# MCU.net
KiCad netlist of a schematic drawn in Altium Designer
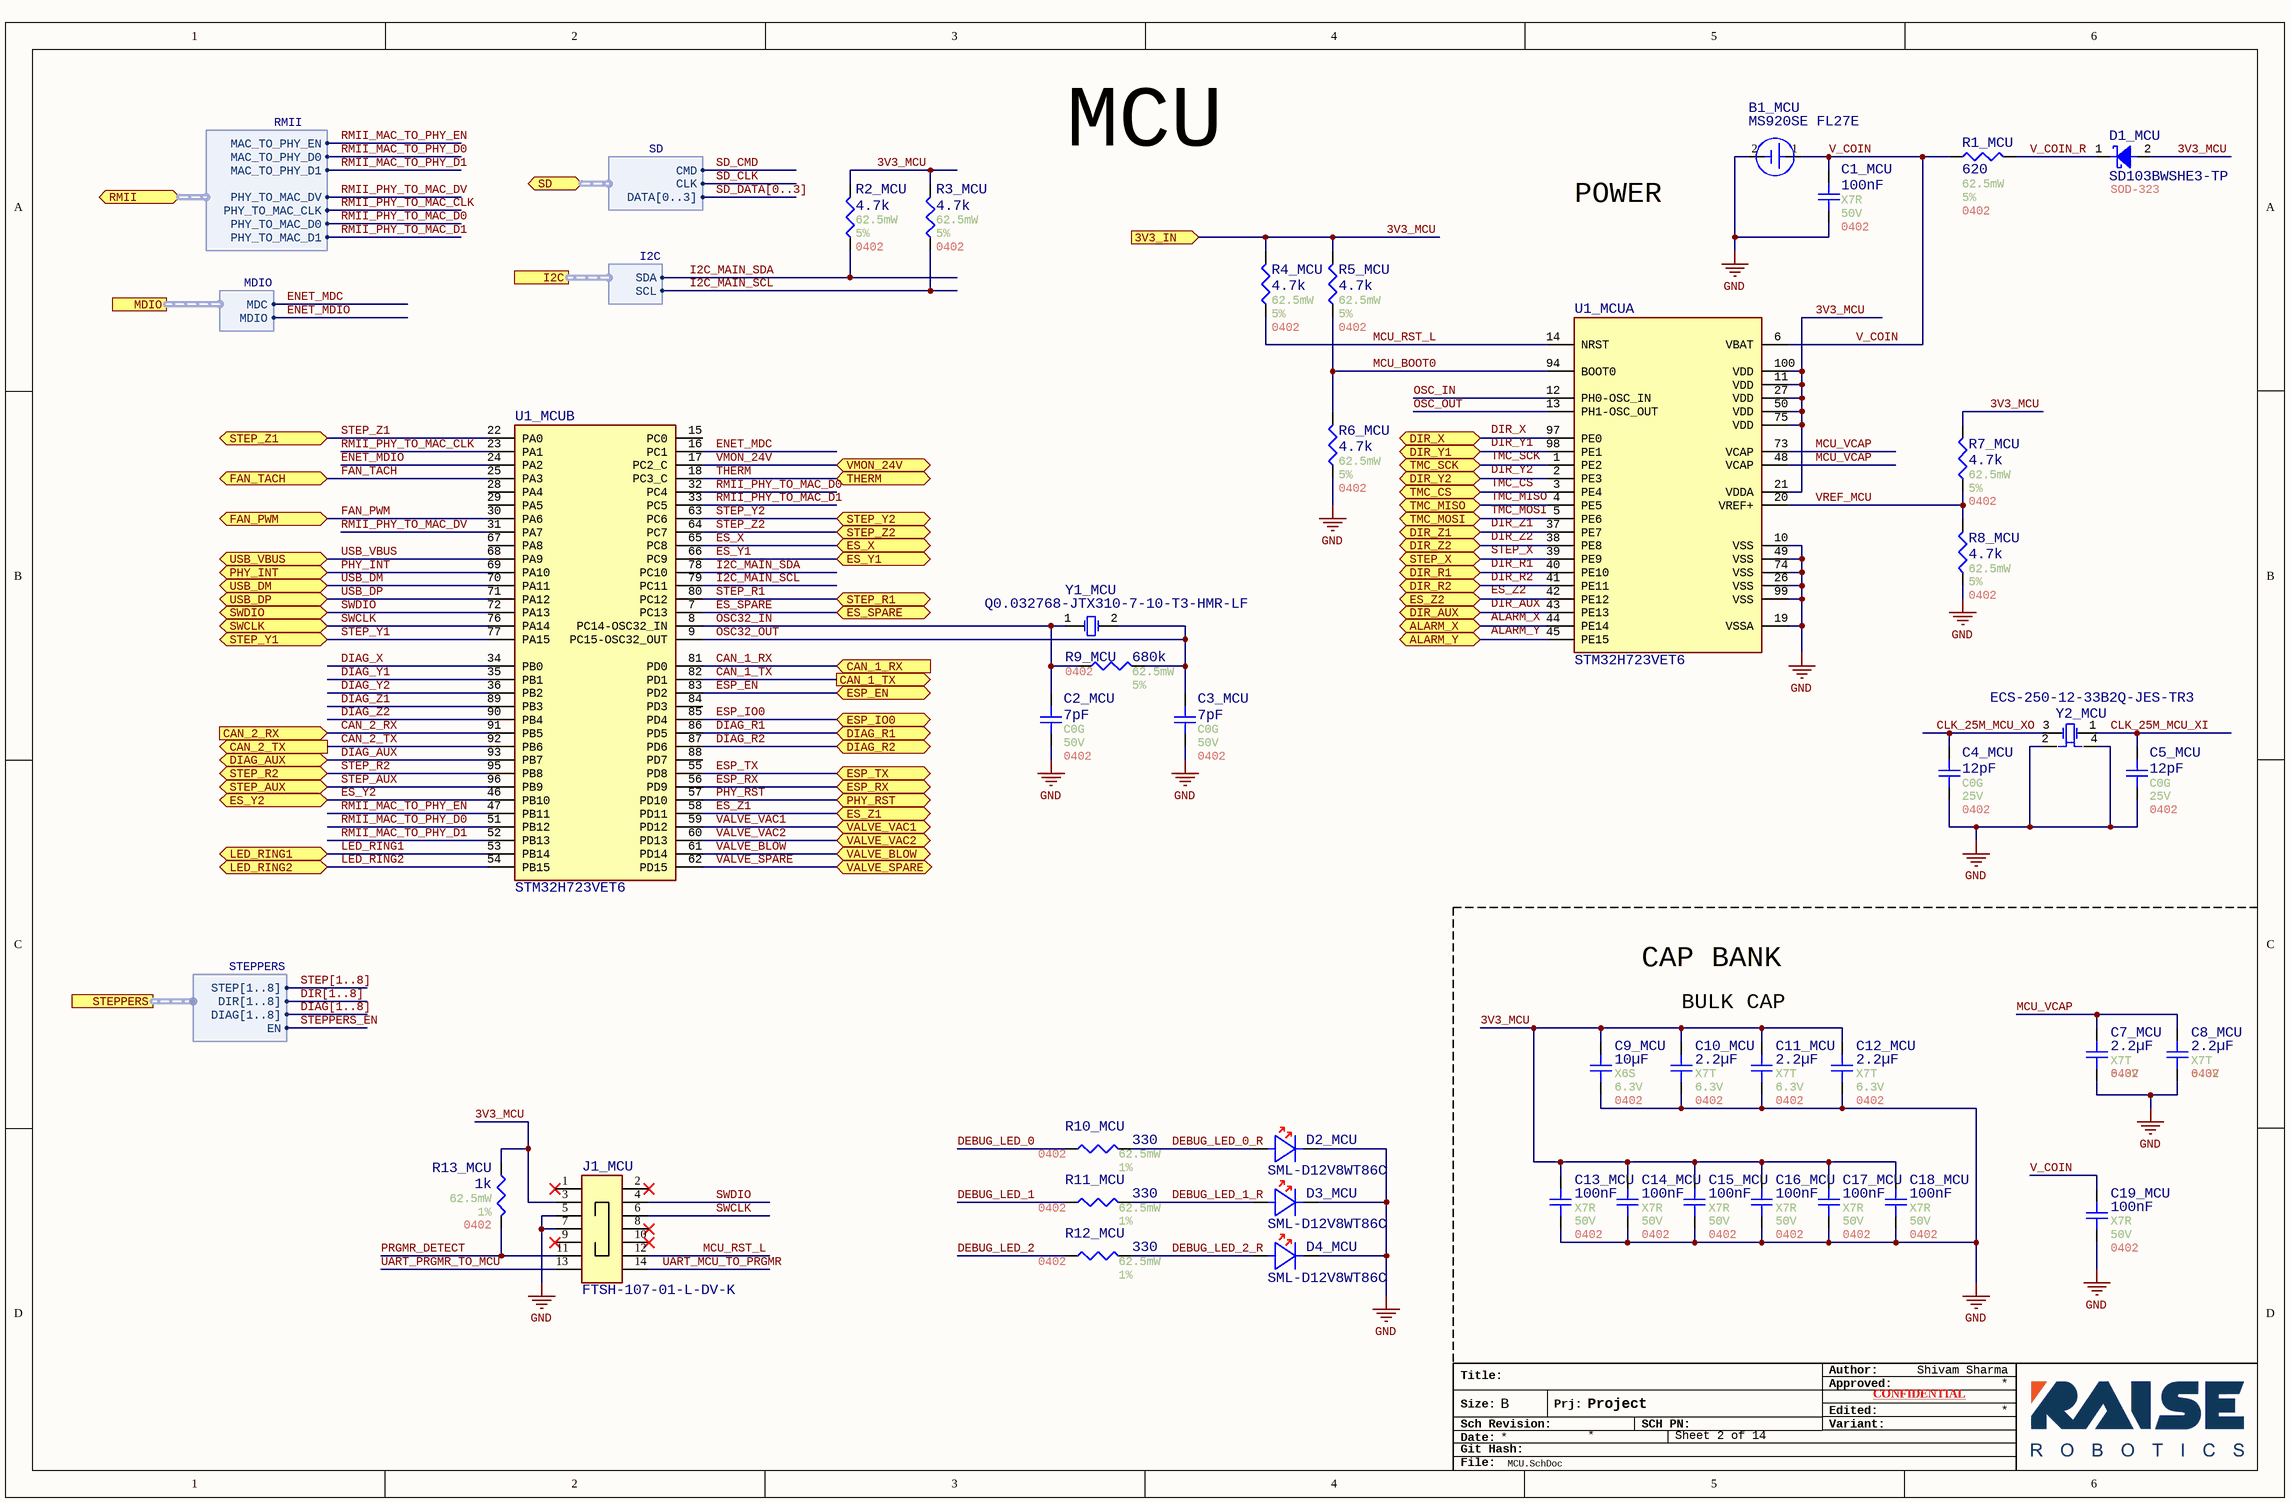
[diagram p0: MCU.SchDoc]

(export (version "E")
  (design (tool "Eeschema 10.0.6"))
  (components
    (comp (ref "B1_MCU")
      (value "MS920SE FL27E")
      (footprint "MS920SE-FL27E")
      (description "Secondary Battery, Manganese Silicon Lithium, 3V, 0.011Ah")
      (libsource (lib "Raise Robotics") (part "Coin Cell"))
    )
    (comp (ref "C1_MCU")
      (value "100nF")
      (footprint "Generic 0402 capacitor")
      (fields
        (field (name "TEMPERATURE COEFFICIENT") "X7R")
        (field (name "VOLTAGE RATING") "50V")
        (field (name "CASE/PACKAGE") "0402")
        (field (name "TOLERANCE") "10%")
        (field (name "Comment") "GRT155R71H104KE01D")
      )
      (libsource (lib "Raise Robotics") (part "Unpolarized Capacitor"))
    )
    (comp (ref "C2_MCU")
      (value "7pF")
      (footprint "Generic 0402 capacitor")
      (fields
        (field (name "TEMPERATURE COEFFICIENT") "C0G")
        (field (name "VOLTAGE RATING") "50V")
        (field (name "CASE/PACKAGE") "0402")
        (field (name "TOLERANCE") "3.5%")
        (field (name "Comment") "GCM1555C1H7R0CA16J")
      )
      (libsource (lib "Raise Robotics") (part "Unpolarized Capacitor"))
    )
    (comp (ref "C3_MCU")
      (value "7pF")
      (footprint "Generic 0402 capacitor")
      (fields
        (field (name "TEMPERATURE COEFFICIENT") "C0G")
        (field (name "VOLTAGE RATING") "50V")
        (field (name "CASE/PACKAGE") "0402")
        (field (name "TOLERANCE") "3.5%")
        (field (name "Comment") "GCM1555C1H7R0CA16J")
      )
      (libsource (lib "Raise Robotics") (part "Unpolarized Capacitor"))
    )
    (comp (ref "C4_MCU")
      (value "12pF")
      (footprint "Generic 0402 capacitor")
      (fields
        (field (name "TEMPERATURE COEFFICIENT") "C0G")
        (field (name "VOLTAGE RATING") "25V")
        (field (name "CASE/PACKAGE") "0402")
        (field (name "TOLERANCE") "5%")
        (field (name "Comment") "GRT1555C1E120JA02J")
      )
      (libsource (lib "Raise Robotics") (part "Unpolarized Capacitor"))
    )
    (comp (ref "C5_MCU")
      (value "12pF")
      (footprint "Generic 0402 capacitor")
      (fields
        (field (name "TEMPERATURE COEFFICIENT") "C0G")
        (field (name "VOLTAGE RATING") "25V")
        (field (name "CASE/PACKAGE") "0402")
        (field (name "TOLERANCE") "5%")
        (field (name "Comment") "GRT1555C1E120JA02J")
      )
      (libsource (lib "Raise Robotics") (part "Unpolarized Capacitor"))
    )
    (comp (ref "C7_MCU")
      (value "2.2µF")
      (footprint "Generic 0402 capacitor")
      (description "Mlcc, 2.2 Uf, # 20 %, 0402, 6.3V, X7T, T&r Q200")
      (fields
        (field (name "TEMPERATURE COEFFICIENT") "X7T")
        (field (name "VOLTAGE RATING") "6.3V")
        (field (name "CASE/PACKAGE") "0402")
        (field (name "TOLERANCE") "20%")
        (field (name "Comment") "MAASJ105CD7225MFCA01")
      )
      (libsource (lib "Raise Robotics") (part "Unpolarized Capacitor"))
    )
    (comp (ref "C8_MCU")
      (value "2.2µF")
      (footprint "Generic 0402 capacitor")
      (description "Mlcc, 2.2 Uf, # 20 %, 0402, 6.3V, X7T, T&r Q200")
      (fields
        (field (name "TEMPERATURE COEFFICIENT") "X7T")
        (field (name "VOLTAGE RATING") "6.3V")
        (field (name "CASE/PACKAGE") "0402")
        (field (name "TOLERANCE") "20%")
        (field (name "Comment") "MAASJ105CD7225MFCA01")
      )
      (libsource (lib "Raise Robotics") (part "Unpolarized Capacitor"))
    )
    (comp (ref "C9_MCU")
      (value "10µF")
      (footprint "Generic 0402 capacitor")
      (description "Multilayer Ceramic Capacitors MLCC - SMD/SMT 0402 10uF 6.3VDC 20% X6S AEC-Q200")
      (fields
        (field (name "TEMPERATURE COEFFICIENT") "X6S")
        (field (name "VOLTAGE RATING") "6.3V")
        (field (name "CASE/PACKAGE") "0402")
        (field (name "TOLERANCE") "20%")
        (field (name "Comment") "GRT155C80J106ME13J")
      )
      (libsource (lib "Raise Robotics") (part "Unpolarized Capacitor"))
    )
    (comp (ref "C10_MCU")
      (value "2.2µF")
      (footprint "Generic 0402 capacitor")
      (description "Mlcc, 2.2 Uf, # 20 %, 0402, 6.3V, X7T, T&r Q200")
      (fields
        (field (name "TEMPERATURE COEFFICIENT") "X7T")
        (field (name "VOLTAGE RATING") "6.3V")
        (field (name "CASE/PACKAGE") "0402")
        (field (name "TOLERANCE") "20%")
        (field (name "Comment") "MAASJ105CD7225MFCA01")
      )
      (libsource (lib "Raise Robotics") (part "Unpolarized Capacitor"))
    )
    (comp (ref "C11_MCU")
      (value "2.2µF")
      (footprint "Generic 0402 capacitor")
      (description "Mlcc, 2.2 Uf, # 20 %, 0402, 6.3V, X7T, T&r Q200")
      (fields
        (field (name "TEMPERATURE COEFFICIENT") "X7T")
        (field (name "VOLTAGE RATING") "6.3V")
        (field (name "CASE/PACKAGE") "0402")
        (field (name "TOLERANCE") "20%")
        (field (name "Comment") "MAASJ105CD7225MFCA01")
      )
      (libsource (lib "Raise Robotics") (part "Unpolarized Capacitor"))
    )
    (comp (ref "C12_MCU")
      (value "2.2µF")
      (footprint "Generic 0402 capacitor")
      (description "Mlcc, 2.2 Uf, # 20 %, 0402, 6.3V, X7T, T&r Q200")
      (fields
        (field (name "TEMPERATURE COEFFICIENT") "X7T")
        (field (name "VOLTAGE RATING") "6.3V")
        (field (name "CASE/PACKAGE") "0402")
        (field (name "TOLERANCE") "20%")
        (field (name "Comment") "MAASJ105CD7225MFCA01")
      )
      (libsource (lib "Raise Robotics") (part "Unpolarized Capacitor"))
    )
    (comp (ref "C13_MCU")
      (value "100nF")
      (footprint "Generic 0402 capacitor")
      (fields
        (field (name "TEMPERATURE COEFFICIENT") "X7R")
        (field (name "VOLTAGE RATING") "50V")
        (field (name "CASE/PACKAGE") "0402")
        (field (name "TOLERANCE") "10%")
        (field (name "Comment") "GRT155R71H104KE01D")
      )
      (libsource (lib "Raise Robotics") (part "Unpolarized Capacitor"))
    )
    (comp (ref "C14_MCU")
      (value "100nF")
      (footprint "Generic 0402 capacitor")
      (fields
        (field (name "TEMPERATURE COEFFICIENT") "X7R")
        (field (name "VOLTAGE RATING") "50V")
        (field (name "CASE/PACKAGE") "0402")
        (field (name "TOLERANCE") "10%")
        (field (name "Comment") "GRT155R71H104KE01D")
      )
      (libsource (lib "Raise Robotics") (part "Unpolarized Capacitor"))
    )
    (comp (ref "C15_MCU")
      (value "100nF")
      (footprint "Generic 0402 capacitor")
      (fields
        (field (name "TEMPERATURE COEFFICIENT") "X7R")
        (field (name "VOLTAGE RATING") "50V")
        (field (name "CASE/PACKAGE") "0402")
        (field (name "TOLERANCE") "10%")
        (field (name "Comment") "GRT155R71H104KE01D")
      )
      (libsource (lib "Raise Robotics") (part "Unpolarized Capacitor"))
    )
    (comp (ref "C16_MCU")
      (value "100nF")
      (footprint "Generic 0402 capacitor")
      (fields
        (field (name "TEMPERATURE COEFFICIENT") "X7R")
        (field (name "VOLTAGE RATING") "50V")
        (field (name "CASE/PACKAGE") "0402")
        (field (name "TOLERANCE") "10%")
        (field (name "Comment") "GRT155R71H104KE01D")
      )
      (libsource (lib "Raise Robotics") (part "Unpolarized Capacitor"))
    )
    (comp (ref "C17_MCU")
      (value "100nF")
      (footprint "Generic 0402 capacitor")
      (fields
        (field (name "TEMPERATURE COEFFICIENT") "X7R")
        (field (name "VOLTAGE RATING") "50V")
        (field (name "CASE/PACKAGE") "0402")
        (field (name "TOLERANCE") "10%")
        (field (name "Comment") "GRT155R71H104KE01D")
      )
      (libsource (lib "Raise Robotics") (part "Unpolarized Capacitor"))
    )
    (comp (ref "C18_MCU")
      (value "100nF")
      (footprint "Generic 0402 capacitor")
      (fields
        (field (name "TEMPERATURE COEFFICIENT") "X7R")
        (field (name "VOLTAGE RATING") "50V")
        (field (name "CASE/PACKAGE") "0402")
        (field (name "TOLERANCE") "10%")
        (field (name "Comment") "GRT155R71H104KE01D")
      )
      (libsource (lib "Raise Robotics") (part "Unpolarized Capacitor"))
    )
    (comp (ref "C19_MCU")
      (value "100nF")
      (footprint "Generic 0402 capacitor")
      (fields
        (field (name "TEMPERATURE COEFFICIENT") "X7R")
        (field (name "VOLTAGE RATING") "50V")
        (field (name "CASE/PACKAGE") "0402")
        (field (name "TOLERANCE") "10%")
        (field (name "Comment") "GRT155R71H104KE01D")
      )
      (libsource (lib "Raise Robotics") (part "Unpolarized Capacitor"))
    )
    (comp (ref "D1_MCU")
      (value "SD103BWSHE3-TP")
      (footprint "SOD-323")
      (description "Rectifier Diode, Schottky, 1 Phase, 1 Element, 0.35A, 30V V(RRM), Silicon")
      (fields (field (name "CASE/PACKAGE") "SOD-323"))
      (libsource (lib "Raise Robotics") (part "Generic 2 pin Diode"))
    )
    (comp (ref "D2_MCU")
      (value "SML-D12V8WT86C")
      (footprint "FP-SML-D12-MFG")
      (description "Red 630nm LED Indication - Discrete 2.2V 0603 (1608 Metric)")
      (libsource (lib "Raise Robotics") (part "LED Red"))
    )
    (comp (ref "D3_MCU")
      (value "SML-D12V8WT86C")
      (footprint "FP-SML-D12-MFG")
      (description "Red 630nm LED Indication - Discrete 2.2V 0603 (1608 Metric)")
      (libsource (lib "Raise Robotics") (part "LED Red"))
    )
    (comp (ref "D4_MCU")
      (value "SML-D12V8WT86C")
      (footprint "FP-SML-D12-MFG")
      (description "Red 630nm LED Indication - Discrete 2.2V 0603 (1608 Metric)")
      (libsource (lib "Raise Robotics") (part "LED Red"))
    )
    (comp (ref "J1_MCU")
      (value "FTSH-107-01-L-DV-K")
      (footprint "FTSH-107-01-L-DV-K-TR")
      (fields (field (name "MANUFACTURER") "Samtec"))
      (libsource (lib "Raise Robotics") (part "FTSH-107-01-L-DV-K-A"))
    )
    (comp (ref "R1_MCU")
      (value "620")
      (footprint "Generic 0402 Resistor")
      (fields
        (field (name "POWER") "62.5mW")
        (field (name "TOLERANCE") "5%")
        (field (name "CASE/PACKAGE") "0402")
        (field (name "Comment") "RC0402JR-07620RL")
      )
      (libsource (lib "Raise Robotics") (part "Resistor"))
    )
    (comp (ref "R2_MCU")
      (value "4.7k")
      (footprint "Generic 0402 Resistor")
      (fields
        (field (name "POWER") "62.5mW")
        (field (name "TOLERANCE") "5%")
        (field (name "CASE/PACKAGE") "0402")
        (field (name "MANUFACTURER PART NUMBER") "Blank")
        (field (name "Comment") "WR04X472JTL")
      )
      (libsource (lib "Raise Robotics") (part "Resistor"))
    )
    (comp (ref "R3_MCU")
      (value "4.7k")
      (footprint "Generic 0402 Resistor")
      (fields
        (field (name "POWER") "62.5mW")
        (field (name "TOLERANCE") "5%")
        (field (name "CASE/PACKAGE") "0402")
        (field (name "MANUFACTURER PART NUMBER") "Blank")
        (field (name "Comment") "WR04X472JTL")
      )
      (libsource (lib "Raise Robotics") (part "Resistor"))
    )
    (comp (ref "R4_MCU")
      (value "4.7k")
      (footprint "Generic 0402 Resistor")
      (fields
        (field (name "POWER") "62.5mW")
        (field (name "TOLERANCE") "5%")
        (field (name "CASE/PACKAGE") "0402")
        (field (name "MANUFACTURER PART NUMBER") "Blank")
        (field (name "Comment") "WR04X472JTL")
      )
      (libsource (lib "Raise Robotics") (part "Resistor"))
    )
    (comp (ref "R5_MCU")
      (value "4.7k")
      (footprint "Generic 0402 Resistor")
      (fields
        (field (name "POWER") "62.5mW")
        (field (name "TOLERANCE") "5%")
        (field (name "CASE/PACKAGE") "0402")
        (field (name "MANUFACTURER PART NUMBER") "Blank")
        (field (name "Comment") "WR04X472JTL")
      )
      (libsource (lib "Raise Robotics") (part "Resistor"))
    )
    (comp (ref "R6_MCU")
      (value "4.7k")
      (footprint "Generic 0402 Resistor")
      (fields
        (field (name "POWER") "62.5mW")
        (field (name "TOLERANCE") "5%")
        (field (name "CASE/PACKAGE") "0402")
        (field (name "MANUFACTURER PART NUMBER") "Blank")
        (field (name "Comment") "WR04X472JTL")
      )
      (libsource (lib "Raise Robotics") (part "Resistor"))
    )
    (comp (ref "R7_MCU")
      (value "4.7k")
      (footprint "Generic 0402 Resistor")
      (fields
        (field (name "POWER") "62.5mW")
        (field (name "TOLERANCE") "5%")
        (field (name "CASE/PACKAGE") "0402")
        (field (name "MANUFACTURER PART NUMBER") "Blank")
        (field (name "Comment") "WR04X472JTL")
      )
      (libsource (lib "Raise Robotics") (part "Resistor"))
    )
    (comp (ref "R8_MCU")
      (value "4.7k")
      (footprint "Generic 0402 Resistor")
      (fields
        (field (name "POWER") "62.5mW")
        (field (name "TOLERANCE") "5%")
        (field (name "CASE/PACKAGE") "0402")
        (field (name "MANUFACTURER PART NUMBER") "Blank")
        (field (name "Comment") "WR04X472JTL")
      )
      (libsource (lib "Raise Robotics") (part "Resistor"))
    )
    (comp (ref "R9_MCU")
      (value "680k")
      (footprint "Generic 0402 Resistor")
      (fields
        (field (name "POWER") "62.5mW")
        (field (name "TOLERANCE") "5%")
        (field (name "CASE/PACKAGE") "0402")
        (field (name "Comment") "AC0402JR-07680KL")
      )
      (libsource (lib "Raise Robotics") (part "Resistor"))
    )
    (comp (ref "R10_MCU")
      (value "330")
      (footprint "Generic 0402 Resistor")
      (description "Res Thick Film 0402 330 Ohm 1% 0.063W ±100ppm/°C Molded SMD Paper T/R")
      (fields
        (field (name "POWER") "62.5mW")
        (field (name "TOLERANCE") "1%")
        (field (name "CASE/PACKAGE") "0402")
        (field (name "Comment") "RMCF0402FT330R")
      )
      (libsource (lib "Raise Robotics") (part "Resistor"))
    )
    (comp (ref "R11_MCU")
      (value "330")
      (footprint "Generic 0402 Resistor")
      (description "Res Thick Film 0402 330 Ohm 1% 0.063W ±100ppm/°C Molded SMD Paper T/R")
      (fields
        (field (name "POWER") "62.5mW")
        (field (name "TOLERANCE") "1%")
        (field (name "CASE/PACKAGE") "0402")
        (field (name "Comment") "RMCF0402FT330R")
      )
      (libsource (lib "Raise Robotics") (part "Resistor"))
    )
    (comp (ref "R12_MCU")
      (value "330")
      (footprint "Generic 0402 Resistor")
      (description "Res Thick Film 0402 330 Ohm 1% 0.063W ±100ppm/°C Molded SMD Paper T/R")
      (fields
        (field (name "POWER") "62.5mW")
        (field (name "TOLERANCE") "1%")
        (field (name "CASE/PACKAGE") "0402")
        (field (name "Comment") "RMCF0402FT330R")
      )
      (libsource (lib "Raise Robotics") (part "Resistor"))
    )
    (comp (ref "R13_MCU")
      (value "1k")
      (footprint "Generic 0402 Resistor")
      (fields
        (field (name "POWER") "62.5mW")
        (field (name "TOLERANCE") "1%")
        (field (name "CASE/PACKAGE") "0402")
        (field (name "MANUFACTURER PART NUMBER") "Blank")
        (field (name "Comment") "WR04X1001FTL")
      )
      (libsource (lib "Raise Robotics") (part "Resistor"))
    )
    (comp (ref "U1_MCU")
      (value "STM32H723VET6")
      (footprint "STM32H723VxT")
      (description "MCU 32-bit ARM Cortex M7 RISC 512KB Flash 1.8V/2.5V/3.3V 100-Pin LQFP Tray")
      (libsource (lib "Raise Robotics") (part "STM32H723VET6"))
    )
    (comp (ref "Y1_MCU")
      (value "Q0.032768-JTX310-7-10-T3-HMR-LF")
      (footprint "JTX310")
      (description "Parallel - Fundamental Quartz Crystal, 0.032768MHz Nom")
      (libsource (lib "Raise Robotics") (part "XTAL-2"))
    )
    (comp (ref "Y2_MCU")
      (value "ECS-250-12-33B2Q-JES-TR3")
      (footprint "ECS-250-12-33B2Q-JES-TR3")
      (description "Crystal 25.000 Mhz 12PF SMD")
      (libsource (lib "") (part "XTAL-2_1"))
    )
  )
  (nets
    (net (code "30") (name "/3V3_MCU") (class "Default")
      (node (ref "C10_MCU") (pin "2") (pinfunction "2_2") (pintype "passive"))
      (node (ref "C11_MCU") (pin "2") (pinfunction "2_2") (pintype "passive"))
      (node (ref "C12_MCU") (pin "2") (pinfunction "2_2") (pintype "passive"))
      (node (ref "C13_MCU") (pin "2") (pinfunction "2_2") (pintype "passive"))
      (node (ref "C14_MCU") (pin "2") (pinfunction "2_2") (pintype "passive"))
      (node (ref "C15_MCU") (pin "2") (pinfunction "2_2") (pintype "passive"))
      (node (ref "C16_MCU") (pin "2") (pinfunction "2_2") (pintype "passive"))
      (node (ref "C17_MCU") (pin "2") (pinfunction "2_2") (pintype "passive"))
      (node (ref "C18_MCU") (pin "2") (pinfunction "2_2") (pintype "passive"))
      (node (ref "C9_MCU") (pin "2") (pinfunction "2_2") (pintype "passive"))
      (node (ref "D1_MCU") (pin "2") (pinfunction "A_2") (pintype "passive"))
      (node (ref "J1_MCU") (pin "3") (pinfunction "3_3") (pintype "passive"))
      (node (ref "R13_MCU") (pin "2") (pinfunction "2_2") (pintype "passive"))
      (node (ref "R2_MCU") (pin "2") (pinfunction "2_2") (pintype "passive"))
      (node (ref "R3_MCU") (pin "2") (pinfunction "2_2") (pintype "passive"))
      (node (ref "R4_MCU") (pin "2") (pinfunction "2_2") (pintype "passive"))
      (node (ref "R5_MCU") (pin "2") (pinfunction "2_2") (pintype "passive"))
      (node (ref "R7_MCU") (pin "2") (pinfunction "2_2") (pintype "passive"))
      (node (ref "U1_MCU") (pin "100") (pinfunction "VDD_100") (pintype "passive"))
      (node (ref "U1_MCU") (pin "11") (pinfunction "VDD_11") (pintype "passive"))
      (node (ref "U1_MCU") (pin "21") (pinfunction "VDDA_21") (pintype "passive"))
      (node (ref "U1_MCU") (pin "27") (pinfunction "VDD_27") (pintype "passive"))
      (node (ref "U1_MCU") (pin "50") (pinfunction "VDD_50") (pintype "passive"))
      (node (ref "U1_MCU") (pin "75") (pinfunction "VDD_75") (pintype "passive"))
    )
    (net (code "31") (name "/ALARM_X") (class "Default")
      (node (ref "U1_MCU") (pin "44") (pinfunction "PE14_44") (pintype "passive"))
    )
    (net (code "32") (name "/ALARM_Y") (class "Default")
      (node (ref "U1_MCU") (pin "45") (pinfunction "PE15_45") (pintype "passive"))
    )
    (net (code "33") (name "/CAN_1_RX") (class "Default")
      (node (ref "U1_MCU") (pin "81") (pinfunction "PD0_81") (pintype "passive"))
    )
    (net (code "34") (name "/CAN_1_TX") (class "Default")
      (node (ref "U1_MCU") (pin "82") (pinfunction "PD1_82") (pintype "passive"))
    )
    (net (code "35") (name "/CAN_2_RX") (class "Default")
      (node (ref "U1_MCU") (pin "91") (pinfunction "PB5_91") (pintype "passive"))
    )
    (net (code "36") (name "/CAN_2_TX") (class "Default")
      (node (ref "U1_MCU") (pin "92") (pinfunction "PB6_92") (pintype "passive"))
    )
    (net (code "37") (name "/CLK_25M_MCU_XI") (class "Default")
      (node (ref "C5_MCU") (pin "2") (pinfunction "2_2") (pintype "passive"))
      (node (ref "Y2_MCU") (pin "1") (pinfunction "1_1") (pintype "passive"))
    )
    (net (code "38") (name "/CLK_25M_MCU_XO") (class "Default")
      (node (ref "C4_MCU") (pin "2") (pinfunction "2_2") (pintype "passive"))
      (node (ref "Y2_MCU") (pin "3") (pinfunction "3_3") (pintype "passive"))
    )
    (net (code "39") (name "/DEBUG_LED_0") (class "Default")
      (node (ref "R10_MCU") (pin "1") (pinfunction "1_1") (pintype "passive"))
    )
    (net (code "40") (name "/DEBUG_LED_0_R") (class "Default")
      (node (ref "D2_MCU") (pin "2") (pinfunction "A_2") (pintype "passive"))
      (node (ref "R10_MCU") (pin "2") (pinfunction "2_2") (pintype "passive"))
    )
    (net (code "41") (name "/DEBUG_LED_1") (class "Default")
      (node (ref "R11_MCU") (pin "1") (pinfunction "1_1") (pintype "passive"))
    )
    (net (code "42") (name "/DEBUG_LED_1_R") (class "Default")
      (node (ref "D3_MCU") (pin "2") (pinfunction "A_2") (pintype "passive"))
      (node (ref "R11_MCU") (pin "2") (pinfunction "2_2") (pintype "passive"))
    )
    (net (code "43") (name "/DEBUG_LED_2") (class "Default")
      (node (ref "R12_MCU") (pin "1") (pinfunction "1_1") (pintype "passive"))
    )
    (net (code "44") (name "/DEBUG_LED_2_R") (class "Default")
      (node (ref "D4_MCU") (pin "2") (pinfunction "A_2") (pintype "passive"))
      (node (ref "R12_MCU") (pin "2") (pinfunction "2_2") (pintype "passive"))
    )
    (net (code "46") (name "/DIAG_AUX") (class "Default")
      (node (ref "U1_MCU") (pin "93") (pinfunction "PB7_93") (pintype "passive"))
    )
    (net (code "47") (name "/DIAG_R1") (class "Default")
      (node (ref "U1_MCU") (pin "86") (pinfunction "PD5_86") (pintype "passive"))
    )
    (net (code "48") (name "/DIAG_R2") (class "Default")
      (node (ref "U1_MCU") (pin "87") (pinfunction "PD6_87") (pintype "passive"))
    )
    (net (code "49") (name "/DIAG_X") (class "Default")
      (node (ref "U1_MCU") (pin "34") (pinfunction "PB0_34") (pintype "passive"))
    )
    (net (code "50") (name "/DIAG_Y1") (class "Default")
      (node (ref "U1_MCU") (pin "35") (pinfunction "PB1_35") (pintype "passive"))
    )
    (net (code "51") (name "/DIAG_Y2") (class "Default")
      (node (ref "U1_MCU") (pin "36") (pinfunction "PB2_36") (pintype "passive"))
    )
    (net (code "52") (name "/DIAG_Z1") (class "Default")
      (node (ref "U1_MCU") (pin "89") (pinfunction "PB3_89") (pintype "passive"))
    )
    (net (code "53") (name "/DIAG_Z2") (class "Default")
      (node (ref "U1_MCU") (pin "90") (pinfunction "PB4_90") (pintype "passive"))
    )
    (net (code "55") (name "/DIR_AUX") (class "Default")
      (node (ref "U1_MCU") (pin "43") (pinfunction "PE13_43") (pintype "passive"))
    )
    (net (code "56") (name "/DIR_R1") (class "Default")
      (node (ref "U1_MCU") (pin "40") (pinfunction "PE10_40") (pintype "passive"))
    )
    (net (code "57") (name "/DIR_R2") (class "Default")
      (node (ref "U1_MCU") (pin "41") (pinfunction "PE11_41") (pintype "passive"))
    )
    (net (code "58") (name "/DIR_X") (class "Default")
      (node (ref "U1_MCU") (pin "97") (pinfunction "PE0_97") (pintype "passive"))
    )
    (net (code "59") (name "/DIR_Y1") (class "Default")
      (node (ref "U1_MCU") (pin "98") (pinfunction "PE1_98") (pintype "passive"))
    )
    (net (code "60") (name "/DIR_Y2") (class "Default")
      (node (ref "U1_MCU") (pin "2") (pinfunction "PE3_2") (pintype "passive"))
    )
    (net (code "61") (name "/DIR_Z1") (class "Default")
      (node (ref "U1_MCU") (pin "37") (pinfunction "PE7_37") (pintype "passive"))
    )
    (net (code "62") (name "/DIR_Z2") (class "Default")
      (node (ref "U1_MCU") (pin "38") (pinfunction "PE8_38") (pintype "passive"))
    )
    (net (code "63") (name "/ENET_MDC") (class "Default")
      (node (ref "U1_MCU") (pin "16") (pinfunction "PC1_16") (pintype "passive"))
    )
    (net (code "64") (name "/ENET_MDIO") (class "Default")
      (node (ref "U1_MCU") (pin "24") (pinfunction "PA2_24") (pintype "passive"))
    )
    (net (code "65") (name "/ESP_EN") (class "Default")
      (node (ref "U1_MCU") (pin "83") (pinfunction "PD2_83") (pintype "passive"))
    )
    (net (code "66") (name "/ESP_IO0") (class "Default")
      (node (ref "U1_MCU") (pin "85") (pinfunction "PD4_85") (pintype "passive"))
    )
    (net (code "67") (name "/ESP_RX") (class "Default")
      (node (ref "U1_MCU") (pin "56") (pinfunction "PD9_56") (pintype "passive"))
    )
    (net (code "68") (name "/ESP_TX") (class "Default")
      (node (ref "U1_MCU") (pin "55") (pinfunction "PD8_55") (pintype "passive"))
    )
    (net (code "69") (name "/ES_SPARE") (class "Default")
      (node (ref "U1_MCU") (pin "7") (pinfunction "PC13_7") (pintype "passive"))
    )
    (net (code "70") (name "/ES_X") (class "Default")
      (node (ref "U1_MCU") (pin "65") (pinfunction "PC8_65") (pintype "passive"))
    )
    (net (code "71") (name "/ES_Y1") (class "Default")
      (node (ref "U1_MCU") (pin "66") (pinfunction "PC9_66") (pintype "passive"))
    )
    (net (code "72") (name "/ES_Y2") (class "Default")
      (node (ref "U1_MCU") (pin "46") (pinfunction "PB10_46") (pintype "passive"))
    )
    (net (code "73") (name "/ES_Z1") (class "Default")
      (node (ref "U1_MCU") (pin "58") (pinfunction "PD11_58") (pintype "passive"))
    )
    (net (code "74") (name "/ES_Z2") (class "Default")
      (node (ref "U1_MCU") (pin "42") (pinfunction "PE12_42") (pintype "passive"))
    )
    (net (code "75") (name "/FAN_PWM") (class "Default")
      (node (ref "U1_MCU") (pin "30") (pinfunction "PA6_30") (pintype "passive"))
    )
    (net (code "76") (name "/FAN_TACH") (class "Default")
      (node (ref "U1_MCU") (pin "25") (pinfunction "PA3_25") (pintype "passive"))
    )
    (net (code "77") (name "/I2C_MAIN_SCL") (class "Default")
      (node (ref "R3_MCU") (pin "1") (pinfunction "1_1") (pintype "passive"))
      (node (ref "U1_MCU") (pin "79") (pinfunction "PC11_79") (pintype "passive"))
    )
    (net (code "78") (name "/I2C_MAIN_SDA") (class "Default")
      (node (ref "R2_MCU") (pin "1") (pinfunction "1_1") (pintype "passive"))
      (node (ref "U1_MCU") (pin "78") (pinfunction "PC10_78") (pintype "passive"))
    )
    (net (code "79") (name "/LED_RING1") (class "Default")
      (node (ref "U1_MCU") (pin "53") (pinfunction "PB14_53") (pintype "passive"))
    )
    (net (code "80") (name "/LED_RING2") (class "Default")
      (node (ref "U1_MCU") (pin "54") (pinfunction "PB15_54") (pintype "passive"))
    )
    (net (code "81") (name "/MCU_BOOT0") (class "Default")
      (node (ref "R5_MCU") (pin "1") (pinfunction "1_1") (pintype "passive"))
      (node (ref "R6_MCU") (pin "2") (pinfunction "2_2") (pintype "passive"))
      (node (ref "U1_MCU") (pin "94") (pinfunction "BOOT0_94") (pintype "passive"))
    )
    (net (code "82") (name "/MCU_RST_L") (class "Default")
      (node (ref "J1_MCU") (pin "12") (pinfunction "12_12") (pintype "passive"))
      (node (ref "R4_MCU") (pin "1") (pinfunction "1_1") (pintype "passive"))
      (node (ref "U1_MCU") (pin "14") (pinfunction "NRST_14") (pintype "passive"))
    )
    (net (code "83") (name "/MCU_VCAP") (class "Default")
      (node (ref "C7_MCU") (pin "2") (pinfunction "2_2") (pintype "passive"))
      (node (ref "C8_MCU") (pin "2") (pinfunction "2_2") (pintype "passive"))
      (node (ref "U1_MCU") (pin "48") (pinfunction "VCAP_48") (pintype "passive"))
      (node (ref "U1_MCU") (pin "73") (pinfunction "VCAP_73") (pintype "passive"))
    )
    (net (code "84") (name "/OSC32_IN") (class "Default")
      (node (ref "C2_MCU") (pin "2") (pinfunction "2_2") (pintype "passive"))
      (node (ref "R9_MCU") (pin "1") (pinfunction "1_1") (pintype "passive"))
      (node (ref "U1_MCU") (pin "8") (pinfunction "PC14-OSC32_IN_8") (pintype "passive"))
      (node (ref "Y1_MCU") (pin "1") (pinfunction "1_1") (pintype "passive"))
    )
    (net (code "85") (name "/OSC32_OUT") (class "Default")
      (node (ref "C3_MCU") (pin "2") (pinfunction "2_2") (pintype "passive"))
      (node (ref "R9_MCU") (pin "2") (pinfunction "2_2") (pintype "passive"))
      (node (ref "U1_MCU") (pin "9") (pinfunction "PC15-OSC32_OUT_9") (pintype "passive"))
      (node (ref "Y1_MCU") (pin "2") (pinfunction "2_2") (pintype "passive"))
    )
    (net (code "86") (name "/OSC_IN") (class "Default")
      (node (ref "U1_MCU") (pin "12") (pinfunction "PH0-OSC_IN_12") (pintype "passive"))
    )
    (net (code "87") (name "/OSC_OUT") (class "Default")
      (node (ref "U1_MCU") (pin "13") (pinfunction "PH1-OSC_OUT_13") (pintype "passive"))
    )
    (net (code "88") (name "/PHY_INT") (class "Default")
      (node (ref "U1_MCU") (pin "69") (pinfunction "PA10_69") (pintype "passive"))
    )
    (net (code "89") (name "/PHY_RST") (class "Default")
      (node (ref "U1_MCU") (pin "57") (pinfunction "PD10_57") (pintype "passive"))
    )
    (net (code "90") (name "/PRGMR_DETECT") (class "Default")
      (node (ref "J1_MCU") (pin "11") (pinfunction "11_11") (pintype "passive"))
      (node (ref "R13_MCU") (pin "1") (pinfunction "1_1") (pintype "passive"))
    )
    (net (code "91") (name "/RMII_MAC_TO_PHY_D0") (class "Default")
      (node (ref "U1_MCU") (pin "51") (pinfunction "PB12_51") (pintype "passive"))
    )
    (net (code "92") (name "/RMII_MAC_TO_PHY_D1") (class "Default")
      (node (ref "U1_MCU") (pin "52") (pinfunction "PB13_52") (pintype "passive"))
    )
    (net (code "93") (name "/RMII_MAC_TO_PHY_EN") (class "Default")
      (node (ref "U1_MCU") (pin "47") (pinfunction "PB11_47") (pintype "passive"))
    )
    (net (code "94") (name "/RMII_PHY_TO_MAC_CLK") (class "Default")
      (node (ref "U1_MCU") (pin "23") (pinfunction "PA1_23") (pintype "passive"))
    )
    (net (code "95") (name "/RMII_PHY_TO_MAC_D0") (class "Default")
      (node (ref "U1_MCU") (pin "32") (pinfunction "PC4_32") (pintype "passive"))
    )
    (net (code "96") (name "/RMII_PHY_TO_MAC_D1") (class "Default")
      (node (ref "U1_MCU") (pin "33") (pinfunction "PC5_33") (pintype "passive"))
    )
    (net (code "97") (name "/RMII_PHY_TO_MAC_DV") (class "Default")
      (node (ref "U1_MCU") (pin "31") (pinfunction "PA7_31") (pintype "passive"))
    )
    (net (code "103") (name "/STEP_AUX") (class "Default")
      (node (ref "U1_MCU") (pin "96") (pinfunction "PB9_96") (pintype "passive"))
    )
    (net (code "104") (name "/STEP_R1") (class "Default")
      (node (ref "U1_MCU") (pin "80") (pinfunction "PC12_80") (pintype "passive"))
    )
    (net (code "105") (name "/STEP_R2") (class "Default")
      (node (ref "U1_MCU") (pin "95") (pinfunction "PB8_95") (pintype "passive"))
    )
    (net (code "106") (name "/STEP_X") (class "Default")
      (node (ref "U1_MCU") (pin "39") (pinfunction "PE9_39") (pintype "passive"))
    )
    (net (code "107") (name "/STEP_Y1") (class "Default")
      (node (ref "U1_MCU") (pin "77") (pinfunction "PA15_77") (pintype "passive"))
    )
    (net (code "108") (name "/STEP_Y2") (class "Default")
      (node (ref "U1_MCU") (pin "63") (pinfunction "PC6_63") (pintype "passive"))
    )
    (net (code "109") (name "/STEP_Z1") (class "Default")
      (node (ref "U1_MCU") (pin "22") (pinfunction "PA0_22") (pintype "passive"))
    )
    (net (code "110") (name "/STEP_Z2") (class "Default")
      (node (ref "U1_MCU") (pin "64") (pinfunction "PC7_64") (pintype "passive"))
    )
    (net (code "111") (name "/SWCLK") (class "Default")
      (node (ref "J1_MCU") (pin "6") (pinfunction "6_6") (pintype "passive"))
      (node (ref "U1_MCU") (pin "76") (pinfunction "PA14_76") (pintype "passive"))
    )
    (net (code "112") (name "/SWDIO") (class "Default")
      (node (ref "J1_MCU") (pin "4") (pinfunction "4_4") (pintype "passive"))
      (node (ref "U1_MCU") (pin "72") (pinfunction "PA13_72") (pintype "passive"))
    )
    (net (code "113") (name "/THERM") (class "Default")
      (node (ref "U1_MCU") (pin "18") (pinfunction "PC3_C_18") (pintype "passive"))
    )
    (net (code "114") (name "/TMC_CS") (class "Default")
      (node (ref "U1_MCU") (pin "3") (pinfunction "PE4_3") (pintype "passive"))
    )
    (net (code "115") (name "/TMC_MISO") (class "Default")
      (node (ref "U1_MCU") (pin "4") (pinfunction "PE5_4") (pintype "passive"))
    )
    (net (code "116") (name "/TMC_MOSI") (class "Default")
      (node (ref "U1_MCU") (pin "5") (pinfunction "PE6_5") (pintype "passive"))
    )
    (net (code "117") (name "/TMC_SCK") (class "Default")
      (node (ref "U1_MCU") (pin "1") (pinfunction "PE2_1") (pintype "passive"))
    )
    (net (code "118") (name "/UART_MCU_TO_PRGMR") (class "Default")
      (node (ref "J1_MCU") (pin "14") (pinfunction "14_14") (pintype "passive"))
    )
    (net (code "119") (name "/UART_PRGMR_TO_MCU") (class "Default")
      (node (ref "J1_MCU") (pin "13") (pinfunction "13_13") (pintype "passive"))
    )
    (net (code "120") (name "/USB_DM") (class "Default")
      (node (ref "U1_MCU") (pin "70") (pinfunction "PA11_70") (pintype "passive"))
    )
    (net (code "121") (name "/USB_DP") (class "Default")
      (node (ref "U1_MCU") (pin "71") (pinfunction "PA12_71") (pintype "passive"))
    )
    (net (code "122") (name "/USB_VBUS") (class "Default")
      (node (ref "U1_MCU") (pin "68") (pinfunction "PA9_68") (pintype "passive"))
    )
    (net (code "123") (name "/VALVE_BLOW") (class "Default")
      (node (ref "U1_MCU") (pin "61") (pinfunction "PD14_61") (pintype "passive"))
    )
    (net (code "124") (name "/VALVE_SPARE") (class "Default")
      (node (ref "U1_MCU") (pin "62") (pinfunction "PD15_62") (pintype "passive"))
    )
    (net (code "125") (name "/VALVE_VAC1") (class "Default")
      (node (ref "U1_MCU") (pin "59") (pinfunction "PD12_59") (pintype "passive"))
    )
    (net (code "126") (name "/VALVE_VAC2") (class "Default")
      (node (ref "U1_MCU") (pin "60") (pinfunction "PD13_60") (pintype "passive"))
    )
    (net (code "127") (name "/VMON_24V") (class "Default")
      (node (ref "U1_MCU") (pin "17") (pinfunction "PC2_C_17") (pintype "passive"))
    )
    (net (code "128") (name "/VREF_MCU") (class "Default")
      (node (ref "R7_MCU") (pin "1") (pinfunction "1_1") (pintype "passive"))
      (node (ref "R8_MCU") (pin "2") (pinfunction "2_2") (pintype "passive"))
      (node (ref "U1_MCU") (pin "20") (pinfunction "VREF+_20") (pintype "passive"))
    )
    (net (code "129") (name "/V_COIN") (class "Default")
      (node (ref "B1_MCU") (pin "1") (pinfunction "1_1") (pintype "passive"))
      (node (ref "C19_MCU") (pin "2") (pinfunction "2_2") (pintype "passive"))
      (node (ref "C1_MCU") (pin "2") (pinfunction "2_2") (pintype "passive"))
      (node (ref "R1_MCU") (pin "1") (pinfunction "1_1") (pintype "passive"))
      (node (ref "U1_MCU") (pin "6") (pinfunction "VBAT_6") (pintype "passive"))
    )
    (net (code "130") (name "/V_COIN_R") (class "Default")
      (node (ref "D1_MCU") (pin "1") (pinfunction "C_1") (pintype "passive"))
      (node (ref "R1_MCU") (pin "2") (pinfunction "2_2") (pintype "passive"))
    )
    (net (code "136") (name "GND") (class "Default")
      (node (ref "B1_MCU") (pin "2") (pinfunction "2_2") (pintype "passive"))
      (node (ref "C10_MCU") (pin "1") (pinfunction "1_1") (pintype "passive"))
      (node (ref "C11_MCU") (pin "1") (pinfunction "1_1") (pintype "passive"))
      (node (ref "C12_MCU") (pin "1") (pinfunction "1_1") (pintype "passive"))
      (node (ref "C13_MCU") (pin "1") (pinfunction "1_1") (pintype "passive"))
      (node (ref "C14_MCU") (pin "1") (pinfunction "1_1") (pintype "passive"))
      (node (ref "C15_MCU") (pin "1") (pinfunction "1_1") (pintype "passive"))
      (node (ref "C16_MCU") (pin "1") (pinfunction "1_1") (pintype "passive"))
      (node (ref "C17_MCU") (pin "1") (pinfunction "1_1") (pintype "passive"))
      (node (ref "C18_MCU") (pin "1") (pinfunction "1_1") (pintype "passive"))
      (node (ref "C19_MCU") (pin "1") (pinfunction "1_1") (pintype "passive"))
      (node (ref "C1_MCU") (pin "1") (pinfunction "1_1") (pintype "passive"))
      (node (ref "C2_MCU") (pin "1") (pinfunction "1_1") (pintype "passive"))
      (node (ref "C3_MCU") (pin "1") (pinfunction "1_1") (pintype "passive"))
      (node (ref "C4_MCU") (pin "1") (pinfunction "1_1") (pintype "passive"))
      (node (ref "C5_MCU") (pin "1") (pinfunction "1_1") (pintype "passive"))
      (node (ref "C7_MCU") (pin "1") (pinfunction "1_1") (pintype "passive"))
      (node (ref "C8_MCU") (pin "1") (pinfunction "1_1") (pintype "passive"))
      (node (ref "C9_MCU") (pin "1") (pinfunction "1_1") (pintype "passive"))
      (node (ref "D2_MCU") (pin "1") (pinfunction "C_1") (pintype "passive"))
      (node (ref "D3_MCU") (pin "1") (pinfunction "C_1") (pintype "passive"))
      (node (ref "D4_MCU") (pin "1") (pinfunction "C_1") (pintype "passive"))
      (node (ref "J1_MCU") (pin "5") (pinfunction "5_5") (pintype "passive"))
      (node (ref "J1_MCU") (pin "7") (pinfunction "7_7") (pintype "passive"))
      (node (ref "R6_MCU") (pin "1") (pinfunction "1_1") (pintype "passive"))
      (node (ref "R8_MCU") (pin "1") (pinfunction "1_1") (pintype "passive"))
      (node (ref "U1_MCU") (pin "10") (pinfunction "VSS_10") (pintype "passive"))
      (node (ref "U1_MCU") (pin "19") (pinfunction "VSSA_19") (pintype "passive"))
      (node (ref "U1_MCU") (pin "26") (pinfunction "VSS_26") (pintype "passive"))
      (node (ref "U1_MCU") (pin "49") (pinfunction "VSS_49") (pintype "passive"))
      (node (ref "U1_MCU") (pin "74") (pinfunction "VSS_74") (pintype "passive"))
      (node (ref "U1_MCU") (pin "99") (pinfunction "VSS_99") (pintype "passive"))
      (node (ref "Y2_MCU") (pin "2") (pinfunction "2_2") (pintype "passive"))
      (node (ref "Y2_MCU") (pin "4") (pinfunction "4_4") (pintype "passive"))
    )
    (net (code "137") (name "unconnected-(J1_MCU-Pad1)") (class "Default")
      (node (ref "J1_MCU") (pin "1") (pinfunction "1_1") (pintype "passive+no_connect"))
    )
    (net (code "138") (name "unconnected-(J1_MCU-Pad2)") (class "Default")
      (node (ref "J1_MCU") (pin "2") (pinfunction "2_2") (pintype "passive+no_connect"))
    )
    (net (code "139") (name "unconnected-(J1_MCU-Pad8)") (class "Default")
      (node (ref "J1_MCU") (pin "8") (pinfunction "8_8") (pintype "passive+no_connect"))
    )
    (net (code "140") (name "unconnected-(J1_MCU-Pad9)") (class "Default")
      (node (ref "J1_MCU") (pin "9") (pinfunction "9_9") (pintype "passive+no_connect"))
    )
    (net (code "141") (name "unconnected-(J1_MCU-Pad10)") (class "Default")
      (node (ref "J1_MCU") (pin "10") (pinfunction "10_10") (pintype "passive+no_connect"))
    )
    (net (code "142") (name "unconnected-(U1_MCUB-PA4-Pad28)") (class "Default")
      (node (ref "U1_MCU") (pin "28") (pinfunction "PA4_28") (pintype "passive"))
    )
    (net (code "143") (name "unconnected-(U1_MCUB-PA5-Pad29)") (class "Default")
      (node (ref "U1_MCU") (pin "29") (pinfunction "PA5_29") (pintype "passive"))
    )
    (net (code "144") (name "unconnected-(U1_MCUB-PA8-Pad67)") (class "Default")
      (node (ref "U1_MCU") (pin "67") (pinfunction "PA8_67") (pintype "passive"))
    )
    (net (code "145") (name "unconnected-(U1_MCUB-PC0-Pad15)") (class "Default")
      (node (ref "U1_MCU") (pin "15") (pinfunction "PC0_15") (pintype "passive"))
    )
    (net (code "146") (name "unconnected-(U1_MCUB-PD3-Pad84)") (class "Default")
      (node (ref "U1_MCU") (pin "84") (pinfunction "PD3_84") (pintype "passive"))
    )
    (net (code "147") (name "unconnected-(U1_MCUB-PD7-Pad88)") (class "Default")
      (node (ref "U1_MCU") (pin "88") (pinfunction "PD7_88") (pintype "passive"))
    )
  )
)
